# Sheet1.net
KiCad netlist of a schematic drawn in Altium Designer
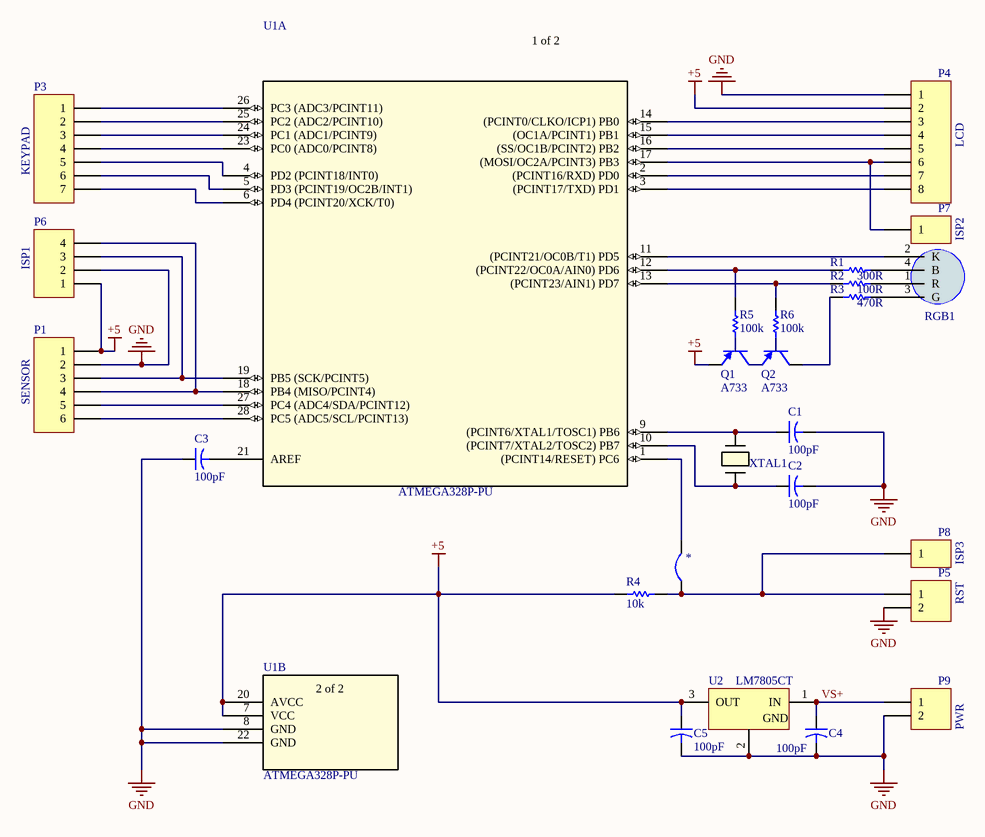
[diagram p0: Sheet1.SchDoc]

(export (version "E")
  (design (tool "Eeschema 10.0.6"))
  (components
    (comp (ref "*") (value "Jumper3") (footprint "JUMPER3") (libsource (lib "Common Parts") (part "Jumper3")))
    (comp (ref "C1")
      (value "100pF")
      (footprint "CAP3")
      (description "Capacitor")
      (fields (field (name "PUBLISHER") "Altium Limited"))
      (libsource (lib "Common Parts") (part "Cap1"))
    )
    (comp (ref "C2")
      (value "100pF")
      (footprint "CAP3")
      (description "Capacitor")
      (fields (field (name "PUBLISHER") "Altium Limited"))
      (libsource (lib "Common Parts") (part "Cap1"))
    )
    (comp (ref "C3")
      (value "100pF")
      (footprint "CAP1")
      (description "Capacitor")
      (fields (field (name "PUBLISHER") "Altium Limited"))
      (libsource (lib "Common Parts") (part "Cap1"))
    )
    (comp (ref "C4")
      (value "100pF")
      (footprint "CAP3")
      (description "Capacitor")
      (fields (field (name "PUBLISHER") "Altium Limited"))
      (libsource (lib "") (part "Cap1_1"))
    )
    (comp (ref "C5")
      (value "100pF")
      (footprint "CAP3")
      (description "Capacitor")
      (fields (field (name "PUBLISHER") "Altium Limited"))
      (libsource (lib "") (part "Cap1_1"))
    )
    (comp (ref "P1")
      (value "SENSOR")
      (footprint "H6")
      (description "Header, 6-Pin")
      (fields (field (name "PUBLISHER") "Altium Limited"))
      (libsource (lib "Miscellaneous Connectors") (part "Header 6"))
    )
    (comp (ref "P3")
      (value "KEYPAD")
      (footprint "H7")
      (description "Header, 7-Pin")
      (fields (field (name "PUBLISHER") "Altium Limited"))
      (libsource (lib "Miscellaneous Connectors") (part "Header 7"))
    )
    (comp (ref "P4")
      (value "LCD")
      (footprint "H8")
      (description "Header, 8-Pin")
      (fields (field (name "PUBLISHER") "Altium Limited"))
      (libsource (lib "Miscellaneous Connectors") (part "Header 8"))
    )
    (comp (ref "P5")
      (value "RST")
      (footprint "H2")
      (description "Header, 2-Pin")
      (fields (field (name "PUBLISHER") "Altium Limited"))
      (libsource (lib "Miscellaneous Connectors") (part "Header 2"))
    )
    (comp (ref "P6")
      (value "ISP1")
      (footprint "H4")
      (description "Header, 4-Pin")
      (fields (field (name "PUBLISHER") "Altium Limited"))
      (libsource (lib "Miscellaneous Connectors") (part "Header 4"))
    )
    (comp (ref "P7")
      (value "ISP2")
      (footprint "H1")
      (description "Header, 1-Pin")
      (fields (field (name "PUBLISHER") "Altium Limited"))
      (libsource (lib "Footprints_lib") (part "Header 1"))
    )
    (comp (ref "P8")
      (value "ISP3")
      (footprint "H1")
      (description "Header, 1-Pin")
      (fields (field (name "PUBLISHER") "Altium Limited"))
      (libsource (lib "Footprints_lib") (part "Header 1"))
    )
    (comp (ref "P9")
      (value "PWR")
      (footprint "H2_PWR")
      (description "Header, 2-Pin")
      (fields (field (name "PUBLISHER") "Altium Limited"))
      (libsource (lib "Footprints_lib") (part "Header 2"))
    )
    (comp (ref "Q1")
      (value "A733")
      (footprint "TO-92_ONS")
      (description "PNP General Purpose Transistor")
      (fields (field (name "PUBLISHER") "Altium Limited"))
      (libsource (lib "Common Parts") (part "A733"))
    )
    (comp (ref "Q2")
      (value "A733")
      (footprint "TO-92_ONS")
      (description "PNP General Purpose Transistor")
      (fields (field (name "PUBLISHER") "Altium Limited"))
      (libsource (lib "Common Parts") (part "A733"))
    )
    (comp (ref "R1")
      (value "300R")
      (footprint "RES")
      (description "Resistor")
      (fields (field (name "PUBLISHER") "Altium Limited"))
      (libsource (lib "Miscellaneous Devices") (part "Res1"))
    )
    (comp (ref "R2")
      (value "100R")
      (footprint "RES")
      (description "Resistor")
      (fields (field (name "PUBLISHER") "Altium Limited"))
      (libsource (lib "Miscellaneous Devices") (part "Res1"))
    )
    (comp (ref "R3")
      (value "470R")
      (footprint "RES")
      (description "Resistor")
      (fields (field (name "PUBLISHER") "Altium Limited"))
      (libsource (lib "Miscellaneous Devices") (part "Res1"))
    )
    (comp (ref "R4")
      (value "10k")
      (footprint "RES")
      (description "Resistor")
      (fields (field (name "PUBLISHER") "Altium Limited"))
      (libsource (lib "Common Parts") (part "Res1"))
    )
    (comp (ref "R5")
      (value "100k")
      (footprint "RES")
      (description "Resistor")
      (fields (field (name "PUBLISHER") "Altium Limited"))
      (libsource (lib "Miscellaneous Devices") (part "Res1"))
    )
    (comp (ref "R6")
      (value "100k")
      (footprint "RES")
      (description "Resistor")
      (fields (field (name "PUBLISHER") "Altium Limited"))
      (libsource (lib "Miscellaneous Devices") (part "Res1"))
    )
    (comp (ref "RGB1") (value "RGB") (footprint "H4") (libsource (lib "Common Parts") (part "RGB")))
    (comp (ref "U1")
      (value "ATMEGA328P-PU")
      (footprint "28P3_ATM")
      (description "No Description Available")
      (fields (field (name "COPYRIGHT") "Copyright (C) 2018 Accelerated Designs. All rights reserved"))
      (libsource (lib "") (part "ATMEGA328P-PU_1"))
    )
    (comp (ref "U2")
      (value "LM7805CT")
      (footprint "FAIR-TO-220-3")
      (description "Positive Voltage Regulator, 5 V, 1 A, -40 to 125 degC, 3-Pin TO-220, RoHS, Tube")
      (fields (field (name "MANUFACTURER") "FairchildSemiconductor"))
      (libsource (lib "Altium Content Vault") (part "FAIR-LM7805CT-TO220-3"))
    )
    (comp (ref "XTAL1")
      (value "9B-11.0592MAAJ-B")
      (footprint "XTAL")
      (description "No Description Available")
      (fields (field (name "COPYRIGHT") "Copyright (C) 2018 Accelerated Designs. All rights reserved"))
      (libsource (lib "Footprints_lib") (part "9B-11.0592MAAJ-B"))
    )
  )
  (nets
    (net (code "1") (name "+5") (class "Default")
      (node (ref "C5") (pin "1") (pinfunction "1_1") (pintype "passive"))
      (node (ref "P1") (pin "1") (pinfunction "1_1") (pintype "passive"))
      (node (ref "P4") (pin "2") (pinfunction "2_2") (pintype "passive"))
      (node (ref "P6") (pin "1") (pinfunction "1_1") (pintype "passive"))
      (node (ref "Q1") (pin "1") (pinfunction "E_1") (pintype "passive"))
      (node (ref "R4") (pin "2") (pinfunction "2_2") (pintype "passive"))
      (node (ref "U1") (pin "20") (pinfunction "AVCC_20") (pintype "power_in"))
      (node (ref "U1") (pin "7") (pinfunction "VCC_7") (pintype "power_in"))
      (node (ref "U2") (pin "3") (pinfunction "OUT_3") (pintype "power_in"))
    )
    (net (code "2") (name "/VS+") (class "Default")
      (node (ref "C4") (pin "1") (pinfunction "1_1") (pintype "passive"))
      (node (ref "P9") (pin "1") (pinfunction "1_1") (pintype "passive"))
      (node (ref "U2") (pin "1") (pinfunction "IN_1") (pintype "power_in"))
    )
    (net (code "3") (name "GND") (class "Default")
      (node (ref "C1") (pin "2") (pinfunction "2_2") (pintype "passive"))
      (node (ref "C2") (pin "2") (pinfunction "2_2") (pintype "passive"))
      (node (ref "C3") (pin "1") (pinfunction "1_1") (pintype "passive"))
      (node (ref "C4") (pin "2") (pinfunction "2_2") (pintype "passive"))
      (node (ref "C5") (pin "2") (pinfunction "2_2") (pintype "passive"))
      (node (ref "P1") (pin "2") (pinfunction "2_2") (pintype "passive"))
      (node (ref "P4") (pin "1") (pinfunction "1_1") (pintype "passive"))
      (node (ref "P5") (pin "2") (pinfunction "2_2") (pintype "passive"))
      (node (ref "P6") (pin "2") (pinfunction "2_2") (pintype "passive"))
      (node (ref "P9") (pin "2") (pinfunction "2_2") (pintype "passive"))
      (node (ref "U1") (pin "22") (pinfunction "GND_22") (pintype "power_in"))
      (node (ref "U1") (pin "8") (pinfunction "GND_8") (pintype "power_in"))
      (node (ref "U2") (pin "2") (pinfunction "GND_2") (pintype "power_in"))
    )
    (net (code "4") (name "Net-(*-Pad1)") (class "Default")
      (node (ref "*") (pin "1") (pinfunction "1_1") (pintype "passive"))
      (node (ref "P5") (pin "1") (pinfunction "1_1") (pintype "passive"))
      (node (ref "P8") (pin "1") (pinfunction "1_1") (pintype "passive"))
      (node (ref "R4") (pin "1") (pinfunction "1_1") (pintype "passive"))
    )
    (net (code "5") (name "Net-(Q1-B)") (class "Default")
      (node (ref "Q1") (pin "3") (pinfunction "B_3") (pintype "passive"))
      (node (ref "R5") (pin "1") (pinfunction "1_1") (pintype "passive"))
    )
    (net (code "6") (name "Net-(Q1-C)") (class "Default")
      (node (ref "Q1") (pin "2") (pinfunction "C_2") (pintype "passive"))
      (node (ref "Q2") (pin "1") (pinfunction "E_1") (pintype "passive"))
    )
    (net (code "7") (name "Net-(Q2-B)") (class "Default")
      (node (ref "Q2") (pin "3") (pinfunction "B_3") (pintype "passive"))
      (node (ref "R6") (pin "1") (pinfunction "1_1") (pintype "passive"))
    )
    (net (code "8") (name "Net-(Q2-C)") (class "Default")
      (node (ref "Q2") (pin "2") (pinfunction "C_2") (pintype "passive"))
      (node (ref "R3") (pin "1") (pinfunction "1_1") (pintype "passive"))
    )
    (net (code "9") (name "Net-(RGB1-B)") (class "Default")
      (node (ref "R1") (pin "2") (pinfunction "2_2") (pintype "passive"))
      (node (ref "RGB1") (pin "4") (pinfunction "B_4") (pintype "passive"))
    )
    (net (code "10") (name "Net-(RGB1-G)") (class "Default")
      (node (ref "R3") (pin "2") (pinfunction "2_2") (pintype "passive"))
      (node (ref "RGB1") (pin "3") (pinfunction "G_3") (pintype "passive"))
    )
    (net (code "11") (name "Net-(RGB1-K)") (class "Default")
      (node (ref "RGB1") (pin "2") (pinfunction "K_2") (pintype "passive"))
      (node (ref "U1") (pin "11") (pinfunction "(PCINT21/OC0B/T1)_PD5_11") (pintype "bidirectional"))
    )
    (net (code "12") (name "Net-(RGB1-R)") (class "Default")
      (node (ref "R2") (pin "2") (pinfunction "2_2") (pintype "passive"))
      (node (ref "RGB1") (pin "1") (pinfunction "R_1") (pintype "passive"))
    )
    (net (code "13") (name "Net-(U1A-(MOSI{slash}OC2A{slash}PCINT3)_PB3)") (class "Default")
      (node (ref "P4") (pin "6") (pinfunction "6_6") (pintype "passive"))
      (node (ref "P7") (pin "1") (pinfunction "1_1") (pintype "passive"))
      (node (ref "U1") (pin "17") (pinfunction "(MOSI/OC2A/PCINT3)_PB3_17") (pintype "bidirectional"))
    )
    (net (code "14") (name "Net-(U1A-(OC1A{slash}PCINT1)_PB1)") (class "Default")
      (node (ref "P4") (pin "4") (pinfunction "4_4") (pintype "passive"))
      (node (ref "U1") (pin "15") (pinfunction "(OC1A/PCINT1)_PB1_15") (pintype "bidirectional"))
    )
    (net (code "15") (name "Net-(U1A-(PCINT0{slash}CLKO{slash}ICP1)_PB0)") (class "Default")
      (node (ref "P4") (pin "3") (pinfunction "3_3") (pintype "passive"))
      (node (ref "U1") (pin "14") (pinfunction "(PCINT0/CLKO/ICP1)_PB0_14") (pintype "bidirectional"))
    )
    (net (code "16") (name "Net-(U1A-(PCINT6{slash}XTAL1{slash}TOSC1)_PB6)") (class "Default")
      (node (ref "C1") (pin "1") (pinfunction "1_1") (pintype "passive"))
      (node (ref "U1") (pin "9") (pinfunction "(PCINT6/XTAL1/TOSC1)_PB6_9") (pintype "bidirectional"))
      (node (ref "XTAL1") (pin "1") (pinfunction "1_1") (pintype "passive"))
    )
    (net (code "17") (name "Net-(U1A-(PCINT7{slash}XTAL2{slash}TOSC2)_PB7)") (class "Default")
      (node (ref "C2") (pin "1") (pinfunction "1_1") (pintype "passive"))
      (node (ref "U1") (pin "10") (pinfunction "(PCINT7/XTAL2/TOSC2)_PB7_10") (pintype "bidirectional"))
      (node (ref "XTAL1") (pin "2") (pinfunction "2_2") (pintype "passive"))
    )
    (net (code "18") (name "Net-(U1A-(PCINT14{slash}RESET)_PC6)") (class "Default")
      (node (ref "*") (pin "2") (pinfunction "2_2") (pintype "passive"))
      (node (ref "U1") (pin "1") (pinfunction "(PCINT14/RESET)_PC6_1") (pintype "bidirectional"))
    )
    (net (code "19") (name "Net-(U1A-(PCINT16{slash}RXD)_PD0)") (class "Default")
      (node (ref "P4") (pin "7") (pinfunction "7_7") (pintype "passive"))
      (node (ref "U1") (pin "2") (pinfunction "(PCINT16/RXD)_PD0_2") (pintype "bidirectional"))
    )
    (net (code "20") (name "Net-(U1A-(PCINT17{slash}TXD)_PD1)") (class "Default")
      (node (ref "P4") (pin "8") (pinfunction "8_8") (pintype "passive"))
      (node (ref "U1") (pin "3") (pinfunction "(PCINT17/TXD)_PD1_3") (pintype "bidirectional"))
    )
    (net (code "21") (name "Net-(U1A-(PCINT22{slash}OC0A{slash}AIN0)_PD6)") (class "Default")
      (node (ref "R1") (pin "1") (pinfunction "1_1") (pintype "passive"))
      (node (ref "R5") (pin "2") (pinfunction "2_2") (pintype "passive"))
      (node (ref "U1") (pin "12") (pinfunction "(PCINT22/OC0A/AIN0)_PD6_12") (pintype "bidirectional"))
    )
    (net (code "22") (name "Net-(U1A-(PCINT23{slash}AIN1)_PD7)") (class "Default")
      (node (ref "R2") (pin "1") (pinfunction "1_1") (pintype "passive"))
      (node (ref "R6") (pin "2") (pinfunction "2_2") (pintype "passive"))
      (node (ref "U1") (pin "13") (pinfunction "(PCINT23/AIN1)_PD7_13") (pintype "bidirectional"))
    )
    (net (code "23") (name "Net-(U1A-(SS{slash}OC1B{slash}PCINT2)_PB2)") (class "Default")
      (node (ref "P4") (pin "5") (pinfunction "5_5") (pintype "passive"))
      (node (ref "U1") (pin "16") (pinfunction "(SS/OC1B/PCINT2)_PB2_16") (pintype "bidirectional"))
    )
    (net (code "24") (name "Net-(U1A-AREF)") (class "Default")
      (node (ref "C3") (pin "2") (pinfunction "2_2") (pintype "passive"))
      (node (ref "U1") (pin "21") (pinfunction "AREF_21") (pintype "passive"))
    )
    (net (code "25") (name "Net-(U1A-PB4_(MISO{slash}PCINT4))") (class "Default")
      (node (ref "P1") (pin "4") (pinfunction "4_4") (pintype "passive"))
      (node (ref "P6") (pin "4") (pinfunction "4_4") (pintype "passive"))
      (node (ref "U1") (pin "18") (pinfunction "PB4_(MISO/PCINT4)_18") (pintype "bidirectional"))
    )
    (net (code "26") (name "Net-(U1A-PB5_(SCK{slash}PCINT5))") (class "Default")
      (node (ref "P1") (pin "3") (pinfunction "3_3") (pintype "passive"))
      (node (ref "P6") (pin "3") (pinfunction "3_3") (pintype "passive"))
      (node (ref "U1") (pin "19") (pinfunction "PB5_(SCK/PCINT5)_19") (pintype "bidirectional"))
    )
    (net (code "27") (name "Net-(U1A-PC0_(ADC0{slash}PCINT8))") (class "Default")
      (node (ref "P3") (pin "4") (pinfunction "4_4") (pintype "passive"))
      (node (ref "U1") (pin "23") (pinfunction "PC0_(ADC0/PCINT8)_23") (pintype "bidirectional"))
    )
    (net (code "28") (name "Net-(U1A-PC1_(ADC1{slash}PCINT9))") (class "Default")
      (node (ref "P3") (pin "3") (pinfunction "3_3") (pintype "passive"))
      (node (ref "U1") (pin "24") (pinfunction "PC1_(ADC1/PCINT9)_24") (pintype "bidirectional"))
    )
    (net (code "29") (name "Net-(U1A-PC2_(ADC2{slash}PCINT10))") (class "Default")
      (node (ref "P3") (pin "2") (pinfunction "2_2") (pintype "passive"))
      (node (ref "U1") (pin "25") (pinfunction "PC2_(ADC2/PCINT10)_25") (pintype "bidirectional"))
    )
    (net (code "30") (name "Net-(U1A-PC3_(ADC3{slash}PCINT11))") (class "Default")
      (node (ref "P3") (pin "1") (pinfunction "1_1") (pintype "passive"))
      (node (ref "U1") (pin "26") (pinfunction "PC3_(ADC3/PCINT11)_26") (pintype "bidirectional"))
    )
    (net (code "31") (name "Net-(U1A-PC4_(ADC4{slash}SDA{slash}PCINT12))") (class "Default")
      (node (ref "P1") (pin "5") (pinfunction "5_5") (pintype "passive"))
      (node (ref "U1") (pin "27") (pinfunction "PC4_(ADC4/SDA/PCINT12)_27") (pintype "bidirectional"))
    )
    (net (code "32") (name "Net-(U1A-PC5_(ADC5{slash}SCL{slash}PCINT13))") (class "Default")
      (node (ref "P1") (pin "6") (pinfunction "6_6") (pintype "passive"))
      (node (ref "U1") (pin "28") (pinfunction "PC5_(ADC5/SCL/PCINT13)_28") (pintype "bidirectional"))
    )
    (net (code "33") (name "Net-(U1A-PD2_(PCINT18{slash}INT0))") (class "Default")
      (node (ref "P3") (pin "5") (pinfunction "5_5") (pintype "passive"))
      (node (ref "U1") (pin "4") (pinfunction "PD2_(PCINT18/INT0)_4") (pintype "bidirectional"))
    )
    (net (code "34") (name "Net-(U1A-PD3_(PCINT19{slash}OC2B{slash}INT1))") (class "Default")
      (node (ref "P3") (pin "6") (pinfunction "6_6") (pintype "passive"))
      (node (ref "U1") (pin "5") (pinfunction "PD3_(PCINT19/OC2B/INT1)_5") (pintype "bidirectional"))
    )
    (net (code "35") (name "Net-(U1A-PD4_(PCINT20{slash}XCK{slash}T0))") (class "Default")
      (node (ref "P3") (pin "7") (pinfunction "7_7") (pintype "passive"))
      (node (ref "U1") (pin "6") (pinfunction "PD4_(PCINT20/XCK/T0)_6") (pintype "bidirectional"))
    )
  )
)
